# AuxHalfH.net
KiCad netlist of a schematic drawn in Altium Designer
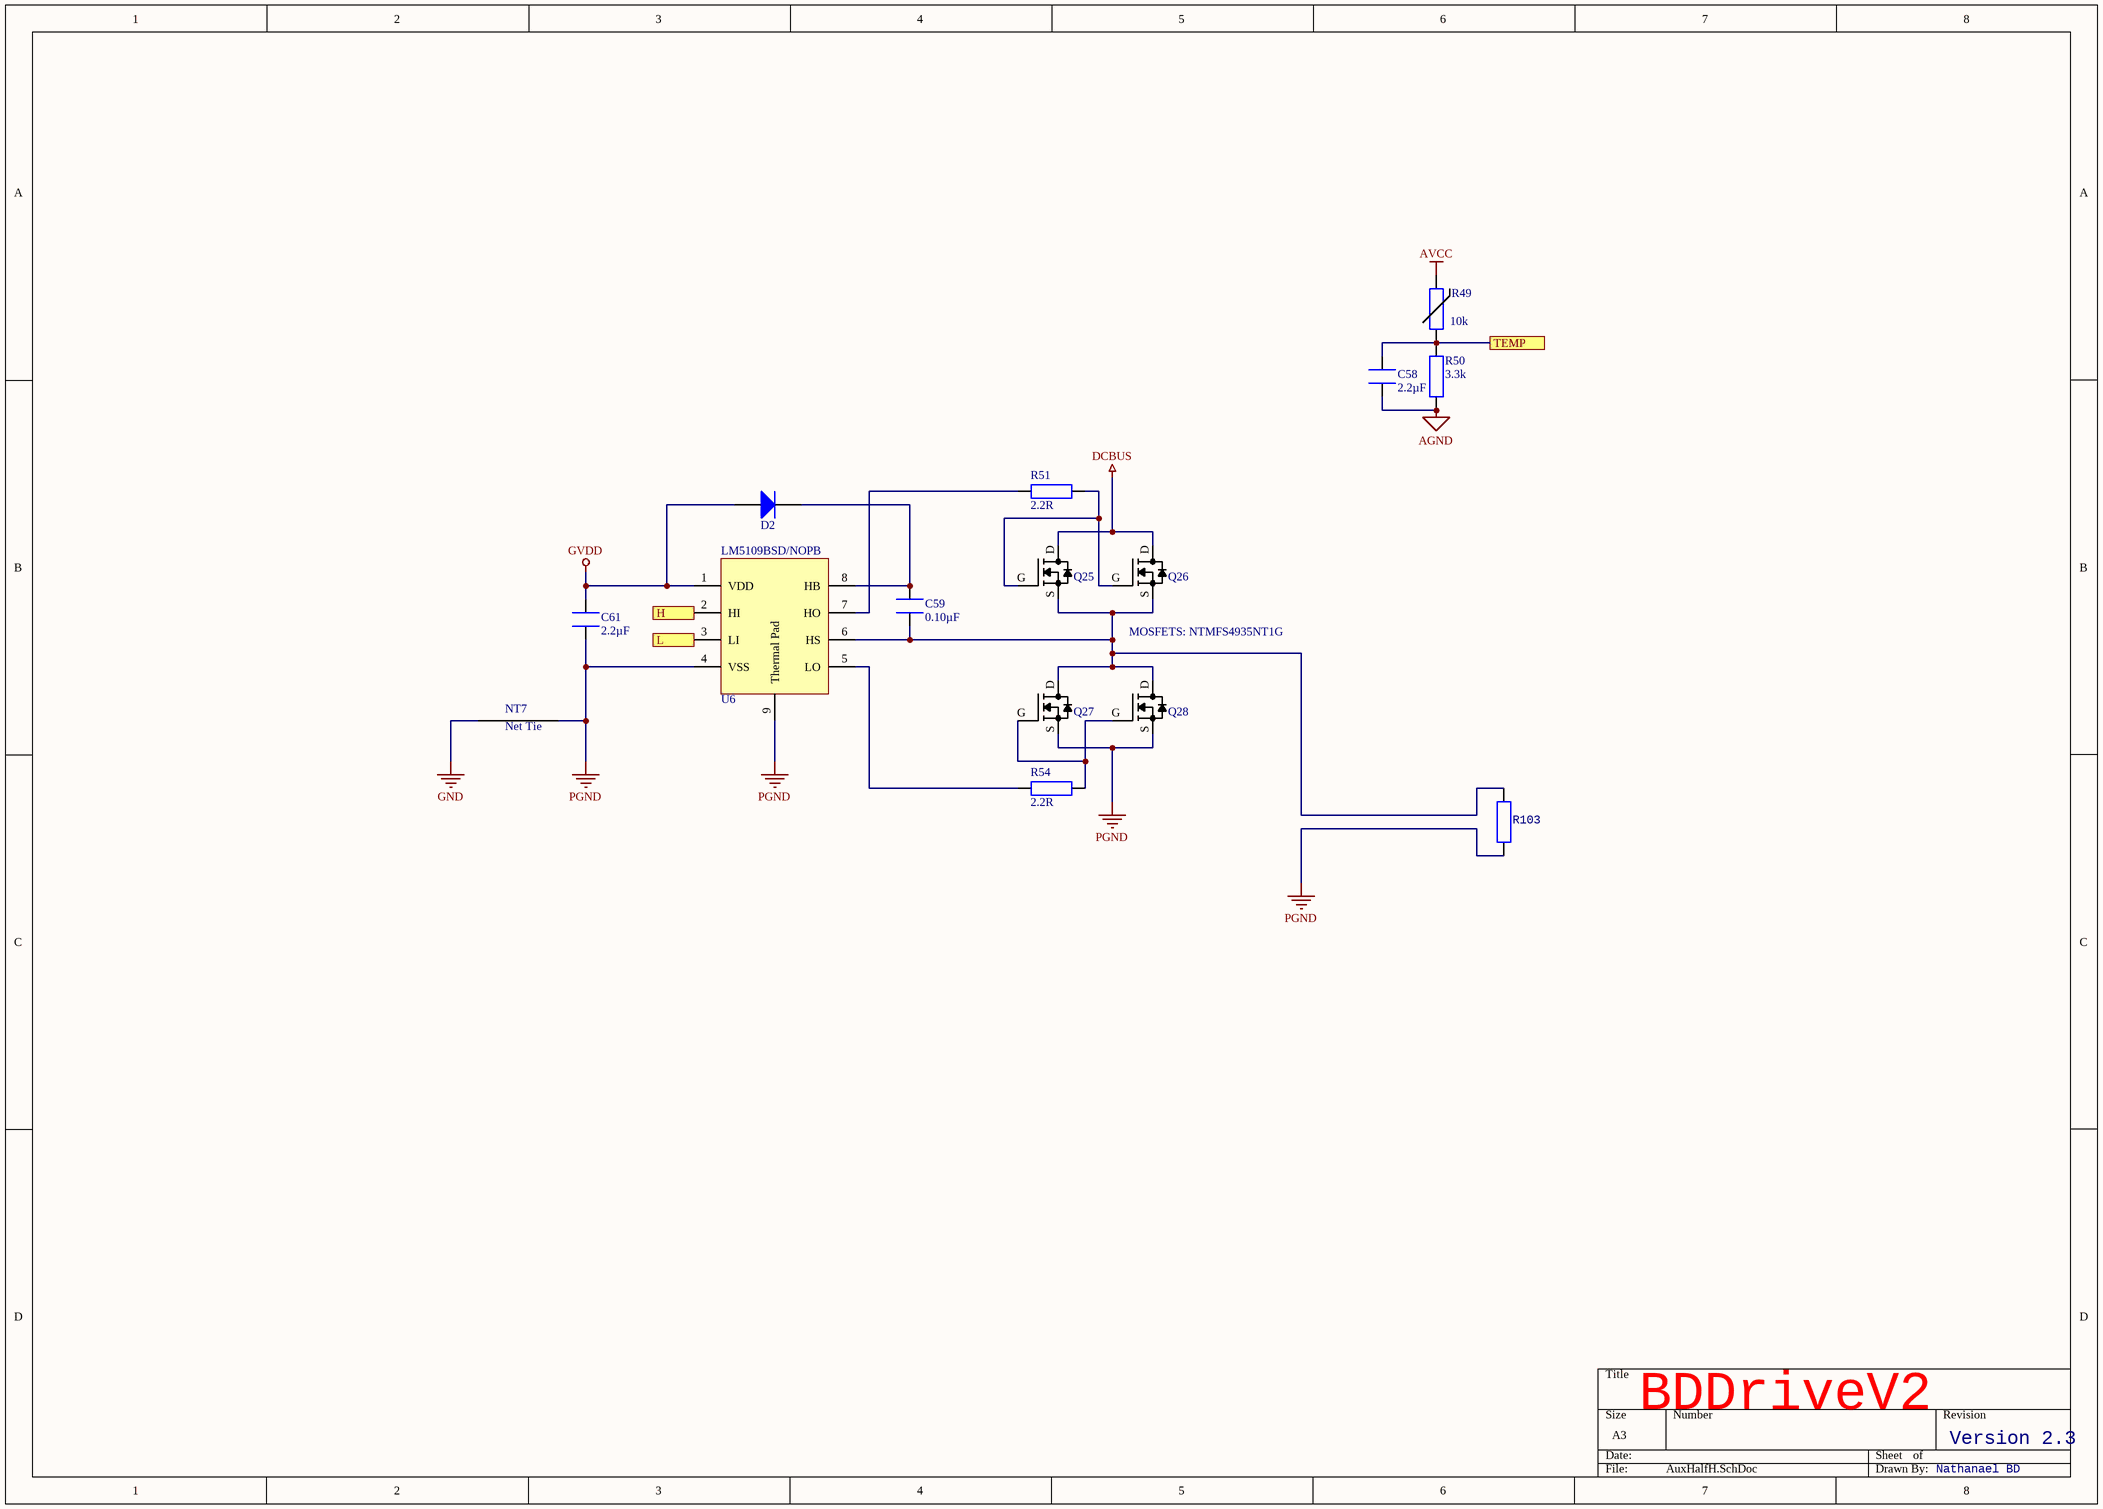
[diagram p0: AuxHalfH.SchDoc]

(export (version "E")
  (design (tool "Eeschema 10.0.6"))
  (components
    (comp (ref "C58")
      (value "2.2µF")
      (footprint "CAPC1608X09L")
      (description "CAP CER 2.2UF 16V X5R 0603")
      (fields
        (field (name "MANUFACTURER") "Murata Electronics North America")
        (field (name "MANUFACTURER PART NUMBER") "GRM188R61C225KE15D")
      )
      (libsource (lib "CustomComponents") (part "GRM188R61C225KE15D"))
    )
    (comp (ref "C59")
      (value "0.10µF")
      (footprint "CAPC1608X09L")
      (description "CAP CER 0.1UF 25V X7R 0603")
      (fields
        (field (name "MANUFACTURER") "Murata Electronics North America")
        (field (name "MANUFACTURER PART NUMBER") "GRM188R71E104KA01D")
      )
      (libsource (lib "CustomComponents") (part "GRM188R71E104KA01D"))
    )
    (comp (ref "C61")
      (value "2.2µF")
      (footprint "CAPC1608X09L")
      (description "CAP CER 2.2UF 16V X5R 0603")
      (fields
        (field (name "MANUFACTURER") "Murata Electronics North America")
        (field (name "MANUFACTURER PART NUMBER") "GRM188R61C225KE15D")
      )
      (libsource (lib "CustomComponents") (part "GRM188R61C225KE15D"))
    )
    (comp (ref "D2")
      (value "~")
      (footprint "DIOM2717X10N")
      (description "Rectifier Diode, Single, 40 V, 1 A, SOD-123FL, 2, 550 mV")
      (libsource (lib "CustomComponents") (part "MBR140SFT1G"))
    )
    (comp (ref "NT7")
      (value "0.25mm")
      (footprint "NetTie_0.25mm")
      (libsource (lib "CustomComponents") (part "NetTie_0.25mm"))
    )
    (comp (ref "Q25")
      (value "NTMFS4935NT1G")
      (footprint "SO8FL_FILL")
      (description "MOSFET N-CH 30V 13A SO8FL")
      (fields (field (name "MANUFACTURER") "ON Semiconductor"))
      (libsource (lib "CustomComponents") (part "NTMFS4935NT1G"))
    )
    (comp (ref "Q26")
      (value "NTMFS4935NT1G")
      (footprint "SO8FL")
      (description "MOSFET N-CH 30V 13A SO8FL")
      (fields (field (name "MANUFACTURER") "ON Semiconductor"))
      (libsource (lib "CustomComponents") (part "NTMFS4935NT1G"))
    )
    (comp (ref "Q27")
      (value "NTMFS4935NT1G")
      (footprint "SO8FL")
      (description "MOSFET N-CH 30V 13A SO8FL")
      (fields (field (name "MANUFACTURER") "ON Semiconductor"))
      (libsource (lib "CustomComponents") (part "NTMFS4935NT1G"))
    )
    (comp (ref "Q28")
      (value "NTMFS4935NT1G")
      (footprint "SO8FL")
      (description "MOSFET N-CH 30V 13A SO8FL")
      (fields (field (name "MANUFACTURER") "ON Semiconductor"))
      (libsource (lib "CustomComponents") (part "NTMFS4935NT1G"))
    )
    (comp (ref "R49")
      (value "10k")
      (footprint "RESC1005X40N")
      (description "THERMISTOR 10K OHM NTC 0402 SMD")
      (fields (field (name "Comment") "NCP15XH103F03RC"))
      (libsource (lib "CustomComponents") (part "NCP15XH103F03RC"))
    )
    (comp (ref "R50")
      (value "3.3k")
      (footprint "RESC1608X55N")
      (description "RES SMD 3.3K OHM 1% 1/10W 0603")
      (fields
        (field (name "MANUFACTURER") "Yageo")
        (field (name "MANUFACTURER PART NUMBER") "RC0603FR-073K3L")
      )
      (libsource (lib "CustomComponents") (part "RC0603FR-073K3L"))
    )
    (comp (ref "R51")
      (value "2.2R")
      (footprint "RESC1608X55N")
      (description "RES SMD 2.2 OHM 1% 1/10W 0603")
      (fields
        (field (name "MANUFACTURER") "Yageo")
        (field (name "MANUFACTURER PART NUMBER") "RC0603FR-072R2L")
      )
      (libsource (lib "CustomComponents") (part "RC0603FR-072R2L"))
    )
    (comp (ref "R54")
      (value "2.2R")
      (footprint "RESC1608X55N")
      (description "RES SMD 2.2 OHM 1% 1/10W 0603")
      (fields
        (field (name "MANUFACTURER") "Yageo")
        (field (name "MANUFACTURER PART NUMBER") "RC0603FR-072R2L")
      )
      (libsource (lib "CustomComponents") (part "RC0603FR-072R2L"))
    )
    (comp (ref "R103")
      (value "1")
      (footprint "SQP500JB-1R0")
      (description "RES 1 OHM 5W 5% AXIAL")
      (libsource (lib "CustomComponents") (part "SQP500JB-1R0"))
    )
    (comp (ref "U6")
      (value "~")
      (footprint "SON80P400X80_HS-9N")
      (description "DRIVER, MOSFET, HALF BRIDGE, WSON-8, 1A")
      (fields (field (name "PARTNUMBER") "LM5109BSD/NOPB"))
      (libsource (lib "CustomComponents") (part "LM5109BSD/NOPB"))
    )
  )
  (nets
    (net (code "1") (name "/H") (class "Default")
      (node (ref "U6") (pin "2") (pinfunction "HI_2") (pintype "passive"))
    )
    (net (code "2") (name "/L") (class "Default")
      (node (ref "U6") (pin "3") (pinfunction "LI_3") (pintype "passive"))
    )
    (net (code "3") (name "/TEMP") (class "Default")
      (node (ref "C58") (pin "2") (pinfunction "2_2") (pintype "passive"))
      (node (ref "R49") (pin "1") (pinfunction "0_1") (pintype "passive"))
      (node (ref "R50") (pin "1") (pinfunction "0_1") (pintype "passive"))
    )
    (net (code "4") (name "AGND") (class "Default")
      (node (ref "C58") (pin "1") (pinfunction "1_1") (pintype "passive"))
      (node (ref "R50") (pin "2") (pinfunction "0_2") (pintype "passive"))
    )
    (net (code "5") (name "AVCC") (class "Default")
      (node (ref "R49") (pin "2") (pinfunction "0_2") (pintype "passive"))
    )
    (net (code "6") (name "DCBUS") (class "Default")
      (node (ref "Q25") (pin "D") (pinfunction "D_D") (pintype "passive"))
      (node (ref "Q26") (pin "D") (pinfunction "D_D") (pintype "passive"))
    )
    (net (code "7") (name "GND") (class "Default") (node (ref "NT7") (pin "1") (pintype "passive")))
    (net (code "8") (name "GVDD") (class "Default")
      (node (ref "C61") (pin "2") (pinfunction "2_2") (pintype "passive"))
      (node (ref "D2") (pin "A") (pinfunction "A_A") (pintype "passive"))
      (node (ref "U6") (pin "1") (pinfunction "VDD_1") (pintype "passive"))
    )
    (net (code "9") (name "Net-(Q25-PadG)") (class "Default")
      (node (ref "Q25") (pin "G") (pinfunction "G_G") (pintype "passive"))
      (node (ref "Q26") (pin "G") (pinfunction "G_G") (pintype "passive"))
      (node (ref "R51") (pin "2") (pinfunction "0_2") (pintype "passive"))
    )
    (net (code "10") (name "Net-(Q27-PadG)") (class "Default")
      (node (ref "Q27") (pin "G") (pinfunction "G_G") (pintype "passive"))
      (node (ref "Q28") (pin "G") (pinfunction "G_G") (pintype "passive"))
      (node (ref "R54") (pin "2") (pinfunction "0_2") (pintype "passive"))
    )
    (net (code "11") (name "Net-(U6-HB)") (class "Default")
      (node (ref "C59") (pin "1") (pinfunction "1_1") (pintype "passive"))
      (node (ref "D2") (pin "K") (pinfunction "K_K") (pintype "passive"))
      (node (ref "U6") (pin "8") (pinfunction "HB_8") (pintype "passive"))
    )
    (net (code "12") (name "Net-(U6-HO)") (class "Default")
      (node (ref "R51") (pin "1") (pinfunction "0_1") (pintype "passive"))
      (node (ref "U6") (pin "7") (pinfunction "HO_7") (pintype "passive"))
    )
    (net (code "13") (name "Net-(U6-HS)") (class "Default")
      (node (ref "C59") (pin "2") (pinfunction "2_2") (pintype "passive"))
      (node (ref "Q25") (pin "S") (pinfunction "S_S") (pintype "passive"))
      (node (ref "Q26") (pin "S") (pinfunction "S_S") (pintype "passive"))
      (node (ref "Q27") (pin "D") (pinfunction "D_D") (pintype "passive"))
      (node (ref "Q28") (pin "D") (pinfunction "D_D") (pintype "passive"))
      (node (ref "R103") (pin "2") (pinfunction "0_2") (pintype "passive"))
      (node (ref "U6") (pin "6") (pinfunction "HS_6") (pintype "passive"))
    )
    (net (code "14") (name "Net-(U6-LO)") (class "Default")
      (node (ref "R54") (pin "1") (pinfunction "0_1") (pintype "passive"))
      (node (ref "U6") (pin "5") (pinfunction "LO_5") (pintype "passive"))
    )
    (net (code "15") (name "PGND") (class "Default")
      (node (ref "C61") (pin "1") (pinfunction "1_1") (pintype "passive"))
      (node (ref "NT7") (pin "2") (pintype "passive"))
      (node (ref "Q27") (pin "S") (pinfunction "S_S") (pintype "passive"))
      (node (ref "Q28") (pin "S") (pinfunction "S_S") (pintype "passive"))
      (node (ref "R103") (pin "1") (pinfunction "0_1") (pintype "passive"))
      (node (ref "U6") (pin "4") (pinfunction "VSS_4") (pintype "passive"))
      (node (ref "U6") (pin "9") (pinfunction "Thermal_Pad_9") (pintype "passive"))
    )
  )
)
